# PCB-BI8-1x10SC3.net
KiCad netlist of a schematic drawn in EAGLE
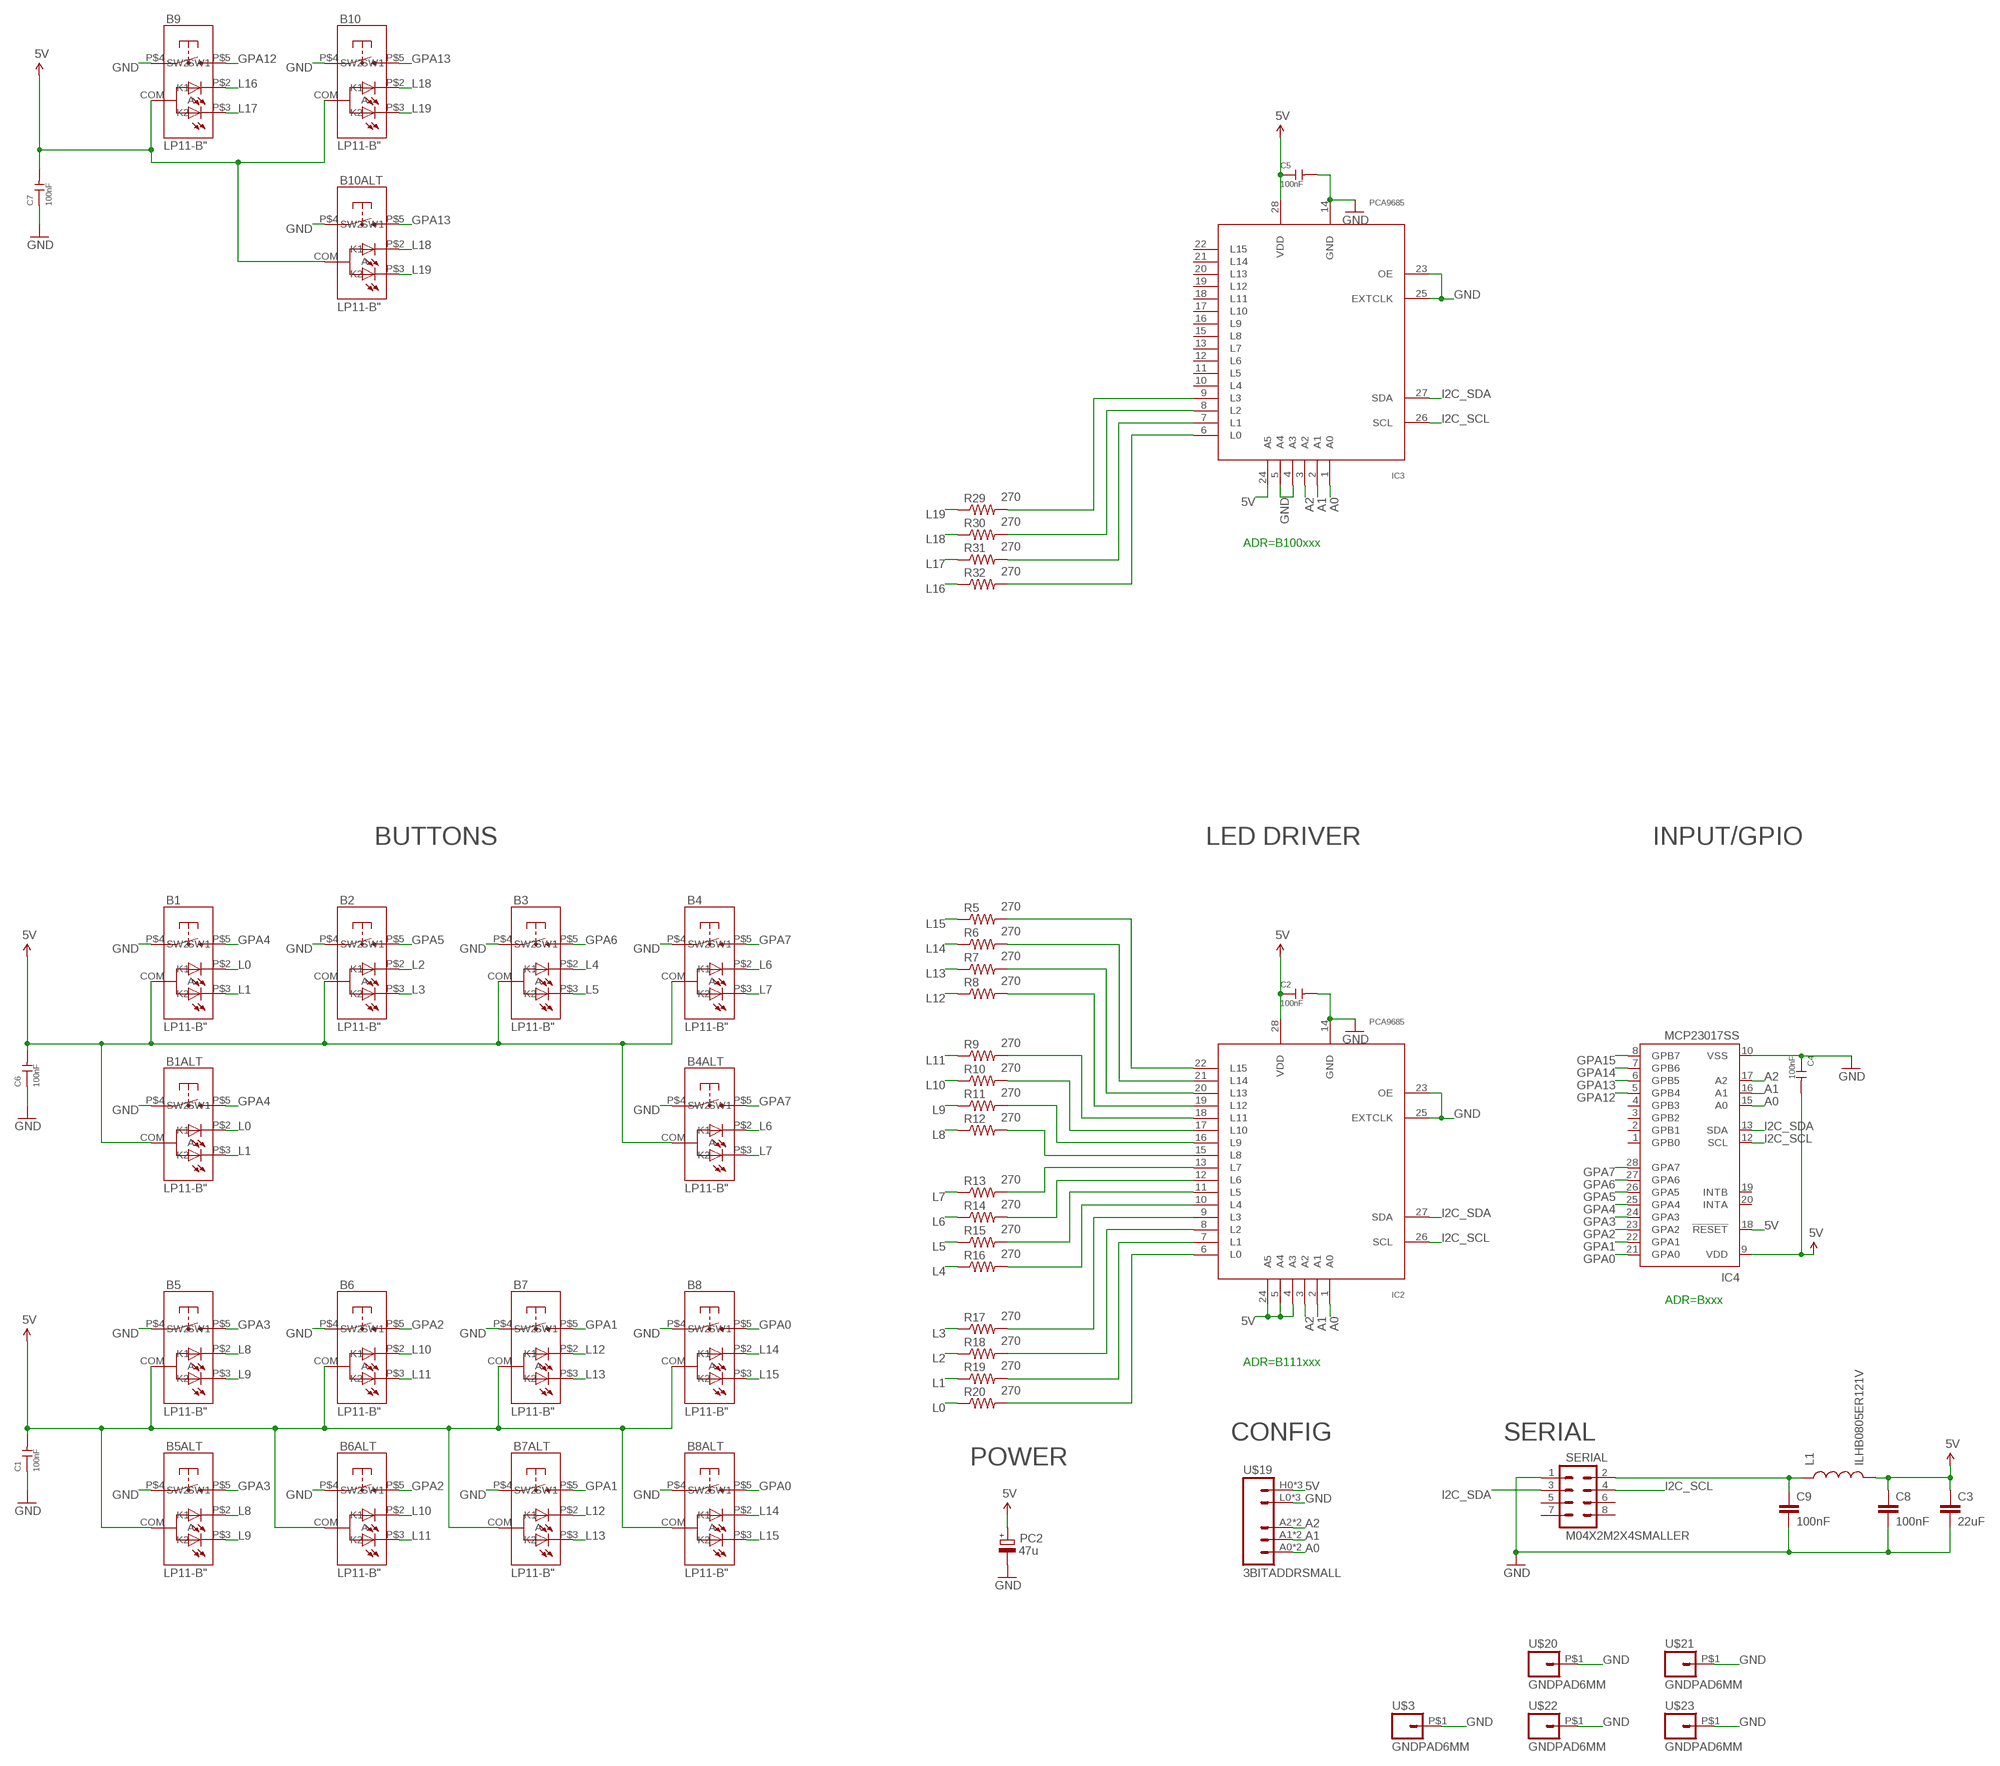
[diagram p0: schematic, sheet 1]

(export (version "E")
  (design (tool "Eeschema 10.0.6"))
  (components
    (comp (ref "B1")
      (value "LP11-B\"")
      (footprint "eagle-import:LP11")
      (libsource (lib "eagle-import") (part "LP11-B{dblquote}"))
    )
    (comp (ref "B1ALT")
      (value "LP11-B\"")
      (footprint "eagle-import:LP11")
      (libsource (lib "eagle-import") (part "LP11-B{dblquote}"))
    )
    (comp (ref "B2")
      (value "LP11-B\"")
      (footprint "eagle-import:LP11")
      (libsource (lib "eagle-import") (part "LP11-B{dblquote}"))
    )
    (comp (ref "B3")
      (value "LP11-B\"")
      (footprint "eagle-import:LP11")
      (libsource (lib "eagle-import") (part "LP11-B{dblquote}"))
    )
    (comp (ref "B4")
      (value "LP11-B\"")
      (footprint "eagle-import:LP11")
      (libsource (lib "eagle-import") (part "LP11-B{dblquote}"))
    )
    (comp (ref "B4ALT")
      (value "LP11-B\"")
      (footprint "eagle-import:LP11")
      (libsource (lib "eagle-import") (part "LP11-B{dblquote}"))
    )
    (comp (ref "B5")
      (value "LP11-B\"")
      (footprint "eagle-import:LP11")
      (libsource (lib "eagle-import") (part "LP11-B{dblquote}"))
    )
    (comp (ref "B5ALT")
      (value "LP11-B\"")
      (footprint "eagle-import:LP11")
      (libsource (lib "eagle-import") (part "LP11-B{dblquote}"))
    )
    (comp (ref "B6")
      (value "LP11-B\"")
      (footprint "eagle-import:LP11")
      (libsource (lib "eagle-import") (part "LP11-B{dblquote}"))
    )
    (comp (ref "B6ALT")
      (value "LP11-B\"")
      (footprint "eagle-import:LP11")
      (libsource (lib "eagle-import") (part "LP11-B{dblquote}"))
    )
    (comp (ref "B7")
      (value "LP11-B\"")
      (footprint "eagle-import:LP11")
      (libsource (lib "eagle-import") (part "LP11-B{dblquote}"))
    )
    (comp (ref "B7ALT")
      (value "LP11-B\"")
      (footprint "eagle-import:LP11")
      (libsource (lib "eagle-import") (part "LP11-B{dblquote}"))
    )
    (comp (ref "B8")
      (value "LP11-B\"")
      (footprint "eagle-import:LP11")
      (libsource (lib "eagle-import") (part "LP11-B{dblquote}"))
    )
    (comp (ref "B8ALT")
      (value "LP11-B\"")
      (footprint "eagle-import:LP11")
      (libsource (lib "eagle-import") (part "LP11-B{dblquote}"))
    )
    (comp (ref "B9")
      (value "LP11-B\"")
      (footprint "eagle-import:LP11")
      (libsource (lib "eagle-import") (part "LP11-B{dblquote}"))
    )
    (comp (ref "B10")
      (value "LP11-B\"")
      (footprint "eagle-import:LP11")
      (libsource (lib "eagle-import") (part "LP11-B{dblquote}"))
    )
    (comp (ref "B10ALT")
      (value "LP11-B\"")
      (footprint "eagle-import:LP11")
      (libsource (lib "eagle-import") (part "LP11-B{dblquote}"))
    )
    (comp (ref "C1")
      (value "100nF")
      (footprint "eagle-import:C0603")
      (libsource (lib "eagle-import") (part "CAP-0603"))
    )
    (comp (ref "C2")
      (value "100nF")
      (footprint "eagle-import:C0603")
      (libsource (lib "eagle-import") (part "CAP-0603"))
    )
    (comp (ref "C3")
      (value "22uF")
      (footprint "eagle-import:0805")
      (libsource (lib "eagle-import") (part "CAP0805"))
    )
    (comp (ref "C4")
      (value "100nF")
      (footprint "eagle-import:C0603")
      (libsource (lib "eagle-import") (part "CAP-0603"))
    )
    (comp (ref "C5")
      (value "100nF")
      (footprint "eagle-import:C0603")
      (libsource (lib "eagle-import") (part "CAP-0603"))
    )
    (comp (ref "C6")
      (value "100nF")
      (footprint "eagle-import:C0603")
      (libsource (lib "eagle-import") (part "CAP-0603"))
    )
    (comp (ref "C7")
      (value "100nF")
      (footprint "eagle-import:C0603")
      (libsource (lib "eagle-import") (part "CAP-0603"))
    )
    (comp (ref "C8")
      (value "100nF")
      (footprint "eagle-import:0603-CAP")
      (libsource (lib "eagle-import") (part "CAP0603-CAP"))
    )
    (comp (ref "C9")
      (value "100nF")
      (footprint "eagle-import:0603-CAP")
      (libsource (lib "eagle-import") (part "CAP0603-CAP"))
    )
    (comp (ref "IC2")
      (value "PCA9685")
      (footprint "eagle-import:TSSOP28")
      (libsource (lib "eagle-import") (part "PCA9685"))
    )
    (comp (ref "IC3")
      (value "PCA9685")
      (footprint "eagle-import:TSSOP28")
      (libsource (lib "eagle-import") (part "PCA9685"))
    )
    (comp (ref "IC4")
      (value "MCP23017SS")
      (footprint "eagle-import:SSOP28")
      (fields
        (field (name "MF") "MICROCHIP")
        (field (name "MPN") "MCP23017-E/SS")
        (field (name "MPN_1") "MCP23017-E/SS")
        (field (name "OC_FARNELL") "1467674")
        (field (name "OC_NEWARK") "31K2960")
      )
      (libsource (lib "eagle-import") (part "MCP23017SS"))
    )
    (comp (ref "L1")
      (value "ILHB0805ER121V")
      (footprint "eagle-import:0805")
      (libsource (lib "eagle-import") (part "INDUCTOR0805"))
    )
    (comp (ref "PC2")
      (value "47u")
      (footprint "eagle-import:PANASONIC_D")
      (libsource (lib "eagle-import") (part "CPOL-EUD"))
    )
    (comp (ref "R5")
      (value "270")
      (footprint "eagle-import:0603-RES")
      (libsource (lib "eagle-import") (part "RESISTOR0603-RES"))
    )
    (comp (ref "R6")
      (value "270")
      (footprint "eagle-import:0603-RES")
      (libsource (lib "eagle-import") (part "RESISTOR0603-RES"))
    )
    (comp (ref "R7")
      (value "270")
      (footprint "eagle-import:0603-RES")
      (libsource (lib "eagle-import") (part "RESISTOR0603-RES"))
    )
    (comp (ref "R8")
      (value "270")
      (footprint "eagle-import:0603-RES")
      (libsource (lib "eagle-import") (part "RESISTOR0603-RES"))
    )
    (comp (ref "R9")
      (value "270")
      (footprint "eagle-import:0603-RES")
      (libsource (lib "eagle-import") (part "RESISTOR0603-RES"))
    )
    (comp (ref "R10")
      (value "270")
      (footprint "eagle-import:0603-RES")
      (libsource (lib "eagle-import") (part "RESISTOR0603-RES"))
    )
    (comp (ref "R11")
      (value "270")
      (footprint "eagle-import:0603-RES")
      (libsource (lib "eagle-import") (part "RESISTOR0603-RES"))
    )
    (comp (ref "R12")
      (value "270")
      (footprint "eagle-import:0603-RES")
      (libsource (lib "eagle-import") (part "RESISTOR0603-RES"))
    )
    (comp (ref "R13")
      (value "270")
      (footprint "eagle-import:0603-RES")
      (libsource (lib "eagle-import") (part "RESISTOR0603-RES"))
    )
    (comp (ref "R14")
      (value "270")
      (footprint "eagle-import:0603-RES")
      (libsource (lib "eagle-import") (part "RESISTOR0603-RES"))
    )
    (comp (ref "R15")
      (value "270")
      (footprint "eagle-import:0603-RES")
      (libsource (lib "eagle-import") (part "RESISTOR0603-RES"))
    )
    (comp (ref "R16")
      (value "270")
      (footprint "eagle-import:0603-RES")
      (libsource (lib "eagle-import") (part "RESISTOR0603-RES"))
    )
    (comp (ref "R17")
      (value "270")
      (footprint "eagle-import:0603-RES")
      (libsource (lib "eagle-import") (part "RESISTOR0603-RES"))
    )
    (comp (ref "R18")
      (value "270")
      (footprint "eagle-import:0603-RES")
      (libsource (lib "eagle-import") (part "RESISTOR0603-RES"))
    )
    (comp (ref "R19")
      (value "270")
      (footprint "eagle-import:0603-RES")
      (libsource (lib "eagle-import") (part "RESISTOR0603-RES"))
    )
    (comp (ref "R20")
      (value "270")
      (footprint "eagle-import:0603-RES")
      (libsource (lib "eagle-import") (part "RESISTOR0603-RES"))
    )
    (comp (ref "R29")
      (value "270")
      (footprint "eagle-import:0603-RES")
      (libsource (lib "eagle-import") (part "RESISTOR0603-RES"))
    )
    (comp (ref "R30")
      (value "270")
      (footprint "eagle-import:0603-RES")
      (libsource (lib "eagle-import") (part "RESISTOR0603-RES"))
    )
    (comp (ref "R31")
      (value "270")
      (footprint "eagle-import:0603-RES")
      (libsource (lib "eagle-import") (part "RESISTOR0603-RES"))
    )
    (comp (ref "R32")
      (value "270")
      (footprint "eagle-import:0603-RES")
      (libsource (lib "eagle-import") (part "RESISTOR0603-RES"))
    )
    (comp (ref "SERIAL")
      (value "M04X2M2X4SMALLER")
      (footprint "eagle-import:M2X4SMALLER")
      (libsource (lib "eagle-import") (part "M04X2M2X4SMALLER"))
    )
    (comp (ref "U$3")
      (value "GNDPAD6MM")
      (footprint "eagle-import:3.2MMPAD6MM")
      (libsource (lib "eagle-import") (part "GNDPAD6MM"))
    )
    (comp (ref "U$19")
      (value "3BITADDRSMALL")
      (footprint "eagle-import:3BITADDR_SMALL")
      (libsource (lib "eagle-import") (part "3BITADDRSMALL"))
    )
    (comp (ref "U$20")
      (value "GNDPAD6MM")
      (footprint "eagle-import:3.2MMPAD6MM")
      (libsource (lib "eagle-import") (part "GNDPAD6MM"))
    )
    (comp (ref "U$21")
      (value "GNDPAD6MM")
      (footprint "eagle-import:3.2MMPAD6MM")
      (libsource (lib "eagle-import") (part "GNDPAD6MM"))
    )
    (comp (ref "U$22")
      (value "GNDPAD6MM")
      (footprint "eagle-import:3.2MMPAD6MM")
      (libsource (lib "eagle-import") (part "GNDPAD6MM"))
    )
    (comp (ref "U$23")
      (value "GNDPAD6MM")
      (footprint "eagle-import:3.2MMPAD6MM")
      (libsource (lib "eagle-import") (part "GNDPAD6MM"))
    )
  )
  (nets
    (net (code "1") (name "/A0") (class "Default")
      (node (ref "IC2") (pin "1") (pinfunction "A0_1") (pintype "input"))
      (node (ref "IC3") (pin "1") (pinfunction "A0_1") (pintype "input"))
      (node (ref "IC4") (pin "15") (pinfunction "A0_15") (pintype "input"))
      (node (ref "U$19") (pin "A0") (pinfunction "A0_A0") (pintype "passive"))
      (node (ref "U$19") (pin "AS0") (pinfunction "A0_AS0") (pintype "passive"))
    )
    (net (code "2") (name "/A1") (class "Default")
      (node (ref "IC2") (pin "2") (pinfunction "A1_2") (pintype "input"))
      (node (ref "IC3") (pin "2") (pinfunction "A1_2") (pintype "input"))
      (node (ref "IC4") (pin "16") (pinfunction "A1_16") (pintype "input"))
      (node (ref "U$19") (pin "A1") (pinfunction "A1_A1") (pintype "passive"))
      (node (ref "U$19") (pin "AS1") (pinfunction "A1_AS1") (pintype "passive"))
    )
    (net (code "3") (name "/A2") (class "Default")
      (node (ref "IC2") (pin "3") (pinfunction "A2_3") (pintype "input"))
      (node (ref "IC3") (pin "3") (pinfunction "A2_3") (pintype "input"))
      (node (ref "IC4") (pin "17") (pinfunction "A2_17") (pintype "input"))
      (node (ref "U$19") (pin "A2") (pinfunction "A2_A2") (pintype "passive"))
      (node (ref "U$19") (pin "AS2") (pinfunction "A2_AS2") (pintype "passive"))
    )
    (net (code "4") (name "/GPA0") (class "Default")
      (node (ref "B8") (pin "P$5") (pinfunction "SW2_P$5") (pintype "bidirectional"))
      (node (ref "B8ALT") (pin "P$5") (pinfunction "SW2_P$5") (pintype "bidirectional"))
      (node (ref "IC4") (pin "21") (pinfunction "GPA0_21") (pintype "bidirectional"))
    )
    (net (code "5") (name "/GPA1") (class "Default")
      (node (ref "B7") (pin "P$5") (pinfunction "SW2_P$5") (pintype "bidirectional"))
      (node (ref "B7ALT") (pin "P$5") (pinfunction "SW2_P$5") (pintype "bidirectional"))
      (node (ref "IC4") (pin "22") (pinfunction "GPA1_22") (pintype "bidirectional"))
    )
    (net (code "6") (name "/GPA2") (class "Default")
      (node (ref "B6") (pin "P$5") (pinfunction "SW2_P$5") (pintype "bidirectional"))
      (node (ref "B6ALT") (pin "P$5") (pinfunction "SW2_P$5") (pintype "bidirectional"))
      (node (ref "IC4") (pin "23") (pinfunction "GPA2_23") (pintype "bidirectional"))
    )
    (net (code "7") (name "/GPA3") (class "Default")
      (node (ref "B5") (pin "P$5") (pinfunction "SW2_P$5") (pintype "bidirectional"))
      (node (ref "B5ALT") (pin "P$5") (pinfunction "SW2_P$5") (pintype "bidirectional"))
      (node (ref "IC4") (pin "24") (pinfunction "GPA3_24") (pintype "bidirectional"))
    )
    (net (code "8") (name "/GPA4") (class "Default")
      (node (ref "B1") (pin "P$5") (pinfunction "SW2_P$5") (pintype "bidirectional"))
      (node (ref "B1ALT") (pin "P$5") (pinfunction "SW2_P$5") (pintype "bidirectional"))
      (node (ref "IC4") (pin "25") (pinfunction "GPA4_25") (pintype "bidirectional"))
    )
    (net (code "9") (name "/GPA5") (class "Default")
      (node (ref "B2") (pin "P$5") (pinfunction "SW2_P$5") (pintype "bidirectional"))
      (node (ref "IC4") (pin "26") (pinfunction "GPA5_26") (pintype "bidirectional"))
    )
    (net (code "10") (name "/GPA6") (class "Default")
      (node (ref "B3") (pin "P$5") (pinfunction "SW2_P$5") (pintype "bidirectional"))
      (node (ref "IC4") (pin "27") (pinfunction "GPA6_27") (pintype "bidirectional"))
    )
    (net (code "11") (name "/GPA7") (class "Default")
      (node (ref "B4") (pin "P$5") (pinfunction "SW2_P$5") (pintype "bidirectional"))
      (node (ref "B4ALT") (pin "P$5") (pinfunction "SW2_P$5") (pintype "bidirectional"))
      (node (ref "IC4") (pin "28") (pinfunction "GPA7_28") (pintype "bidirectional"))
    )
    (net (code "12") (name "/GPA12") (class "Default")
      (node (ref "B9") (pin "P$5") (pinfunction "SW2_P$5") (pintype "bidirectional"))
      (node (ref "IC4") (pin "5") (pinfunction "GPB4_5") (pintype "bidirectional"))
    )
    (net (code "13") (name "/GPA13") (class "Default")
      (node (ref "B10") (pin "P$5") (pinfunction "SW2_P$5") (pintype "bidirectional"))
      (node (ref "B10ALT") (pin "P$5") (pinfunction "SW2_P$5") (pintype "bidirectional"))
      (node (ref "IC4") (pin "6") (pinfunction "GPB5_6") (pintype "bidirectional"))
    )
    (net (code "14") (name "/GPA14") (class "Default")
      (node (ref "IC4") (pin "7") (pinfunction "GPB6_7") (pintype "bidirectional"))
    )
    (net (code "15") (name "/GPA15") (class "Default")
      (node (ref "IC4") (pin "8") (pinfunction "GPB7_8") (pintype "bidirectional"))
    )
    (net (code "16") (name "/I2C_SCL") (class "Default")
      (node (ref "IC2") (pin "26") (pinfunction "SCL_26") (pintype "input"))
      (node (ref "IC3") (pin "26") (pinfunction "SCL_26") (pintype "input"))
      (node (ref "IC4") (pin "12") (pinfunction "SCL_12") (pintype "input"))
      (node (ref "SERIAL") (pin "4") (pinfunction "4_4") (pintype "passive"))
    )
    (net (code "17") (name "/I2C_SDA") (class "Default")
      (node (ref "IC2") (pin "27") (pinfunction "SDA_27") (pintype "input"))
      (node (ref "IC3") (pin "27") (pinfunction "SDA_27") (pintype "input"))
      (node (ref "IC4") (pin "13") (pinfunction "SDA_13") (pintype "bidirectional"))
      (node (ref "SERIAL") (pin "3") (pinfunction "3_3") (pintype "passive"))
    )
    (net (code "18") (name "/L0") (class "Default")
      (node (ref "B1") (pin "P$2") (pinfunction "K1_P$2") (pintype "bidirectional"))
      (node (ref "B1ALT") (pin "P$2") (pinfunction "K1_P$2") (pintype "bidirectional"))
      (node (ref "R20") (pin "1") (pinfunction "1_1") (pintype "passive"))
    )
    (net (code "19") (name "/L1") (class "Default")
      (node (ref "B1") (pin "P$3") (pinfunction "K2_P$3") (pintype "bidirectional"))
      (node (ref "B1ALT") (pin "P$3") (pinfunction "K2_P$3") (pintype "bidirectional"))
      (node (ref "R19") (pin "1") (pinfunction "1_1") (pintype "passive"))
    )
    (net (code "20") (name "/L2") (class "Default")
      (node (ref "B2") (pin "P$2") (pinfunction "K1_P$2") (pintype "bidirectional"))
      (node (ref "R18") (pin "1") (pinfunction "1_1") (pintype "passive"))
    )
    (net (code "21") (name "/L3") (class "Default")
      (node (ref "B2") (pin "P$3") (pinfunction "K2_P$3") (pintype "bidirectional"))
      (node (ref "R17") (pin "1") (pinfunction "1_1") (pintype "passive"))
    )
    (net (code "22") (name "/L4") (class "Default")
      (node (ref "B3") (pin "P$2") (pinfunction "K1_P$2") (pintype "bidirectional"))
      (node (ref "R16") (pin "1") (pinfunction "1_1") (pintype "passive"))
    )
    (net (code "23") (name "/L5") (class "Default")
      (node (ref "B3") (pin "P$3") (pinfunction "K2_P$3") (pintype "bidirectional"))
      (node (ref "R15") (pin "1") (pinfunction "1_1") (pintype "passive"))
    )
    (net (code "24") (name "/L6") (class "Default")
      (node (ref "B4") (pin "P$2") (pinfunction "K1_P$2") (pintype "bidirectional"))
      (node (ref "B4ALT") (pin "P$2") (pinfunction "K1_P$2") (pintype "bidirectional"))
      (node (ref "R14") (pin "1") (pinfunction "1_1") (pintype "passive"))
    )
    (net (code "25") (name "/L7") (class "Default")
      (node (ref "B4") (pin "P$3") (pinfunction "K2_P$3") (pintype "bidirectional"))
      (node (ref "B4ALT") (pin "P$3") (pinfunction "K2_P$3") (pintype "bidirectional"))
      (node (ref "R13") (pin "1") (pinfunction "1_1") (pintype "passive"))
    )
    (net (code "26") (name "/L8") (class "Default")
      (node (ref "B5") (pin "P$2") (pinfunction "K1_P$2") (pintype "bidirectional"))
      (node (ref "B5ALT") (pin "P$2") (pinfunction "K1_P$2") (pintype "bidirectional"))
      (node (ref "R12") (pin "1") (pinfunction "1_1") (pintype "passive"))
    )
    (net (code "27") (name "/L9") (class "Default")
      (node (ref "B5") (pin "P$3") (pinfunction "K2_P$3") (pintype "bidirectional"))
      (node (ref "B5ALT") (pin "P$3") (pinfunction "K2_P$3") (pintype "bidirectional"))
      (node (ref "R11") (pin "1") (pinfunction "1_1") (pintype "passive"))
    )
    (net (code "28") (name "/L10") (class "Default")
      (node (ref "B6") (pin "P$2") (pinfunction "K1_P$2") (pintype "bidirectional"))
      (node (ref "B6ALT") (pin "P$2") (pinfunction "K1_P$2") (pintype "bidirectional"))
      (node (ref "R10") (pin "1") (pinfunction "1_1") (pintype "passive"))
    )
    (net (code "29") (name "/L11") (class "Default")
      (node (ref "B6") (pin "P$3") (pinfunction "K2_P$3") (pintype "bidirectional"))
      (node (ref "B6ALT") (pin "P$3") (pinfunction "K2_P$3") (pintype "bidirectional"))
      (node (ref "R9") (pin "1") (pinfunction "1_1") (pintype "passive"))
    )
    (net (code "30") (name "/L12") (class "Default")
      (node (ref "B7") (pin "P$2") (pinfunction "K1_P$2") (pintype "bidirectional"))
      (node (ref "B7ALT") (pin "P$2") (pinfunction "K1_P$2") (pintype "bidirectional"))
      (node (ref "R8") (pin "1") (pinfunction "1_1") (pintype "passive"))
    )
    (net (code "31") (name "/L13") (class "Default")
      (node (ref "B7") (pin "P$3") (pinfunction "K2_P$3") (pintype "bidirectional"))
      (node (ref "B7ALT") (pin "P$3") (pinfunction "K2_P$3") (pintype "bidirectional"))
      (node (ref "R7") (pin "1") (pinfunction "1_1") (pintype "passive"))
    )
    (net (code "32") (name "/L14") (class "Default")
      (node (ref "B8") (pin "P$2") (pinfunction "K1_P$2") (pintype "bidirectional"))
      (node (ref "B8ALT") (pin "P$2") (pinfunction "K1_P$2") (pintype "bidirectional"))
      (node (ref "R6") (pin "1") (pinfunction "1_1") (pintype "passive"))
    )
    (net (code "33") (name "/L15") (class "Default")
      (node (ref "B8") (pin "P$3") (pinfunction "K2_P$3") (pintype "bidirectional"))
      (node (ref "B8ALT") (pin "P$3") (pinfunction "K2_P$3") (pintype "bidirectional"))
      (node (ref "R5") (pin "1") (pinfunction "1_1") (pintype "passive"))
    )
    (net (code "34") (name "/L16") (class "Default")
      (node (ref "B9") (pin "P$2") (pinfunction "K1_P$2") (pintype "bidirectional"))
      (node (ref "R32") (pin "1") (pinfunction "1_1") (pintype "passive"))
    )
    (net (code "35") (name "/L17") (class "Default")
      (node (ref "B9") (pin "P$3") (pinfunction "K2_P$3") (pintype "bidirectional"))
      (node (ref "R31") (pin "1") (pinfunction "1_1") (pintype "passive"))
    )
    (net (code "36") (name "/L18") (class "Default")
      (node (ref "B10") (pin "P$2") (pinfunction "K1_P$2") (pintype "bidirectional"))
      (node (ref "B10ALT") (pin "P$2") (pinfunction "K1_P$2") (pintype "bidirectional"))
      (node (ref "R30") (pin "1") (pinfunction "1_1") (pintype "passive"))
    )
    (net (code "37") (name "/L19") (class "Default")
      (node (ref "B10") (pin "P$3") (pinfunction "K2_P$3") (pintype "bidirectional"))
      (node (ref "B10ALT") (pin "P$3") (pinfunction "K2_P$3") (pintype "bidirectional"))
      (node (ref "R29") (pin "1") (pinfunction "1_1") (pintype "passive"))
    )
    (net (code "38") (name "5V") (class "Default")
      (node (ref "B1") (pin "COM") (pinfunction "A_COM") (pintype "bidirectional"))
      (node (ref "B10") (pin "COM") (pinfunction "A_COM") (pintype "bidirectional"))
      (node (ref "B10ALT") (pin "COM") (pinfunction "A_COM") (pintype "bidirectional"))
      (node (ref "B1ALT") (pin "COM") (pinfunction "A_COM") (pintype "bidirectional"))
      (node (ref "B2") (pin "COM") (pinfunction "A_COM") (pintype "bidirectional"))
      (node (ref "B3") (pin "COM") (pinfunction "A_COM") (pintype "bidirectional"))
      (node (ref "B4") (pin "COM") (pinfunction "A_COM") (pintype "bidirectional"))
      (node (ref "B4ALT") (pin "COM") (pinfunction "A_COM") (pintype "bidirectional"))
      (node (ref "B5") (pin "COM") (pinfunction "A_COM") (pintype "bidirectional"))
      (node (ref "B5ALT") (pin "COM") (pinfunction "A_COM") (pintype "bidirectional"))
      (node (ref "B6") (pin "COM") (pinfunction "A_COM") (pintype "bidirectional"))
      (node (ref "B6ALT") (pin "COM") (pinfunction "A_COM") (pintype "bidirectional"))
      (node (ref "B7") (pin "COM") (pinfunction "A_COM") (pintype "bidirectional"))
      (node (ref "B7ALT") (pin "COM") (pinfunction "A_COM") (pintype "bidirectional"))
      (node (ref "B8") (pin "COM") (pinfunction "A_COM") (pintype "bidirectional"))
      (node (ref "B8ALT") (pin "COM") (pinfunction "A_COM") (pintype "bidirectional"))
      (node (ref "B9") (pin "COM") (pinfunction "A_COM") (pintype "bidirectional"))
      (node (ref "C1") (pin "2") (pinfunction "2_2") (pintype "passive"))
      (node (ref "C2") (pin "1") (pinfunction "1_1") (pintype "passive"))
      (node (ref "C3") (pin "1") (pinfunction "1_1") (pintype "passive"))
      (node (ref "C4") (pin "2") (pinfunction "2_2") (pintype "passive"))
      (node (ref "C5") (pin "1") (pinfunction "1_1") (pintype "passive"))
      (node (ref "C6") (pin "2") (pinfunction "2_2") (pintype "passive"))
      (node (ref "C7") (pin "2") (pinfunction "2_2") (pintype "passive"))
      (node (ref "C8") (pin "1") (pinfunction "1_1") (pintype "passive"))
      (node (ref "IC2") (pin "24") (pinfunction "A5_24") (pintype "input"))
      (node (ref "IC2") (pin "28") (pinfunction "VDD_28") (pintype "power_in"))
      (node (ref "IC2") (pin "4") (pinfunction "A3_4") (pintype "input"))
      (node (ref "IC2") (pin "5") (pinfunction "A4_5") (pintype "input"))
      (node (ref "IC3") (pin "24") (pinfunction "A5_24") (pintype "input"))
      (node (ref "IC3") (pin "28") (pinfunction "VDD_28") (pintype "power_in"))
      (node (ref "IC4") (pin "18") (pinfunction "~{RESET}_18") (pintype "input"))
      (node (ref "IC4") (pin "9") (pinfunction "VDD_9") (pintype "power_in"))
      (node (ref "L1") (pin "2") (pinfunction "2_2") (pintype "passive"))
      (node (ref "PC2") (pin "+") (pinfunction "+_+") (pintype "passive"))
      (node (ref "U$19") (pin "H0") (pinfunction "VCC_H0") (pintype "passive"))
      (node (ref "U$19") (pin "H1") (pinfunction "VCC_H1") (pintype "passive"))
      (node (ref "U$19") (pin "H2") (pinfunction "VCC_H2") (pintype "passive"))
    )
    (net (code "39") (name "GND") (class "Default")
      (node (ref "B1") (pin "P$4") (pinfunction "SW1_P$4") (pintype "bidirectional"))
      (node (ref "B10") (pin "P$4") (pinfunction "SW1_P$4") (pintype "bidirectional"))
      (node (ref "B10ALT") (pin "P$4") (pinfunction "SW1_P$4") (pintype "bidirectional"))
      (node (ref "B1ALT") (pin "P$4") (pinfunction "SW1_P$4") (pintype "bidirectional"))
      (node (ref "B2") (pin "P$4") (pinfunction "SW1_P$4") (pintype "bidirectional"))
      (node (ref "B3") (pin "P$4") (pinfunction "SW1_P$4") (pintype "bidirectional"))
      (node (ref "B4") (pin "P$4") (pinfunction "SW1_P$4") (pintype "bidirectional"))
      (node (ref "B4ALT") (pin "P$4") (pinfunction "SW1_P$4") (pintype "bidirectional"))
      (node (ref "B5") (pin "P$4") (pinfunction "SW1_P$4") (pintype "bidirectional"))
      (node (ref "B5ALT") (pin "P$4") (pinfunction "SW1_P$4") (pintype "bidirectional"))
      (node (ref "B6") (pin "P$4") (pinfunction "SW1_P$4") (pintype "bidirectional"))
      (node (ref "B6ALT") (pin "P$4") (pinfunction "SW1_P$4") (pintype "bidirectional"))
      (node (ref "B7") (pin "P$4") (pinfunction "SW1_P$4") (pintype "bidirectional"))
      (node (ref "B7ALT") (pin "P$4") (pinfunction "SW1_P$4") (pintype "bidirectional"))
      (node (ref "B8") (pin "P$4") (pinfunction "SW1_P$4") (pintype "bidirectional"))
      (node (ref "B8ALT") (pin "P$4") (pinfunction "SW1_P$4") (pintype "bidirectional"))
      (node (ref "B9") (pin "P$4") (pinfunction "SW1_P$4") (pintype "bidirectional"))
      (node (ref "C1") (pin "1") (pinfunction "1_1") (pintype "passive"))
      (node (ref "C2") (pin "2") (pinfunction "2_2") (pintype "passive"))
      (node (ref "C3") (pin "2") (pinfunction "2_2") (pintype "passive"))
      (node (ref "C4") (pin "1") (pinfunction "1_1") (pintype "passive"))
      (node (ref "C5") (pin "2") (pinfunction "2_2") (pintype "passive"))
      (node (ref "C6") (pin "1") (pinfunction "1_1") (pintype "passive"))
      (node (ref "C7") (pin "1") (pinfunction "1_1") (pintype "passive"))
      (node (ref "C8") (pin "2") (pinfunction "2_2") (pintype "passive"))
      (node (ref "C9") (pin "2") (pinfunction "2_2") (pintype "passive"))
      (node (ref "IC2") (pin "14") (pinfunction "GND_14") (pintype "power_in"))
      (node (ref "IC2") (pin "23") (pinfunction "OE_23") (pintype "input"))
      (node (ref "IC2") (pin "25") (pinfunction "EXTCLK_25") (pintype "input"))
      (node (ref "IC3") (pin "14") (pinfunction "GND_14") (pintype "power_in"))
      (node (ref "IC3") (pin "23") (pinfunction "OE_23") (pintype "input"))
      (node (ref "IC3") (pin "25") (pinfunction "EXTCLK_25") (pintype "input"))
      (node (ref "IC3") (pin "4") (pinfunction "A3_4") (pintype "input"))
      (node (ref "IC3") (pin "5") (pinfunction "A4_5") (pintype "input"))
      (node (ref "IC4") (pin "10") (pinfunction "VSS_10") (pintype "power_in"))
      (node (ref "PC2") (pin "-") (pinfunction "-_-") (pintype "passive"))
      (node (ref "SERIAL") (pin "1") (pinfunction "1_1") (pintype "passive"))
      (node (ref "U$19") (pin "L0") (pinfunction "GND_L0") (pintype "passive"))
      (node (ref "U$19") (pin "L1") (pinfunction "GND_L1") (pintype "passive"))
      (node (ref "U$19") (pin "L2") (pinfunction "GND_L2") (pintype "passive"))
      (node (ref "U$20") (pin "P$1") (pinfunction "1_P$1") (pintype "passive"))
      (node (ref "U$21") (pin "P$1") (pinfunction "1_P$1") (pintype "passive"))
      (node (ref "U$22") (pin "P$1") (pinfunction "1_P$1") (pintype "passive"))
      (node (ref "U$23") (pin "P$1") (pinfunction "1_P$1") (pintype "passive"))
      (node (ref "U$3") (pin "P$1") (pinfunction "1_P$1") (pintype "passive"))
    )
    (net (code "40") (name "Net-(C9-Pad1)") (class "Default")
      (node (ref "C9") (pin "1") (pinfunction "1_1") (pintype "passive"))
      (node (ref "L1") (pin "1") (pinfunction "1_1") (pintype "passive"))
      (node (ref "SERIAL") (pin "2") (pinfunction "2_2") (pintype "passive"))
    )
    (net (code "41") (name "Net-(IC2-L0)") (class "Default")
      (node (ref "IC2") (pin "6") (pinfunction "L0_6") (pintype "output"))
      (node (ref "R20") (pin "2") (pinfunction "2_2") (pintype "passive"))
    )
    (net (code "42") (name "Net-(IC2-L1)") (class "Default")
      (node (ref "IC2") (pin "7") (pinfunction "L1_7") (pintype "output"))
      (node (ref "R19") (pin "2") (pinfunction "2_2") (pintype "passive"))
    )
    (net (code "43") (name "Net-(IC2-L2)") (class "Default")
      (node (ref "IC2") (pin "8") (pinfunction "L2_8") (pintype "output"))
      (node (ref "R18") (pin "2") (pinfunction "2_2") (pintype "passive"))
    )
    (net (code "44") (name "Net-(IC2-L3)") (class "Default")
      (node (ref "IC2") (pin "9") (pinfunction "L3_9") (pintype "output"))
      (node (ref "R17") (pin "2") (pinfunction "2_2") (pintype "passive"))
    )
    (net (code "45") (name "Net-(IC2-L4)") (class "Default")
      (node (ref "IC2") (pin "10") (pinfunction "L4_10") (pintype "output"))
      (node (ref "R16") (pin "2") (pinfunction "2_2") (pintype "passive"))
    )
    (net (code "46") (name "Net-(IC2-L5)") (class "Default")
      (node (ref "IC2") (pin "11") (pinfunction "L5_11") (pintype "output"))
      (node (ref "R15") (pin "2") (pinfunction "2_2") (pintype "passive"))
    )
    (net (code "47") (name "Net-(IC2-L6)") (class "Default")
      (node (ref "IC2") (pin "12") (pinfunction "L6_12") (pintype "output"))
      (node (ref "R14") (pin "2") (pinfunction "2_2") (pintype "passive"))
    )
    (net (code "48") (name "Net-(IC2-L7)") (class "Default")
      (node (ref "IC2") (pin "13") (pinfunction "L7_13") (pintype "output"))
      (node (ref "R13") (pin "2") (pinfunction "2_2") (pintype "passive"))
    )
    (net (code "49") (name "Net-(IC2-L8)") (class "Default")
      (node (ref "IC2") (pin "15") (pinfunction "L8_15") (pintype "output"))
      (node (ref "R12") (pin "2") (pinfunction "2_2") (pintype "passive"))
    )
    (net (code "50") (name "Net-(IC2-L9)") (class "Default")
      (node (ref "IC2") (pin "16") (pinfunction "L9_16") (pintype "output"))
      (node (ref "R11") (pin "2") (pinfunction "2_2") (pintype "passive"))
    )
    (net (code "51") (name "Net-(IC2-L10)") (class "Default")
      (node (ref "IC2") (pin "17") (pinfunction "L10_17") (pintype "output"))
      (node (ref "R10") (pin "2") (pinfunction "2_2") (pintype "passive"))
    )
    (net (code "52") (name "Net-(IC2-L11)") (class "Default")
      (node (ref "IC2") (pin "18") (pinfunction "L11_18") (pintype "output"))
      (node (ref "R9") (pin "2") (pinfunction "2_2") (pintype "passive"))
    )
    (net (code "53") (name "Net-(IC2-L12)") (class "Default")
      (node (ref "IC2") (pin "19") (pinfunction "L12_19") (pintype "output"))
      (node (ref "R8") (pin "2") (pinfunction "2_2") (pintype "passive"))
    )
    (net (code "54") (name "Net-(IC2-L13)") (class "Default")
      (node (ref "IC2") (pin "20") (pinfunction "L13_20") (pintype "output"))
      (node (ref "R7") (pin "2") (pinfunction "2_2") (pintype "passive"))
    )
    (net (code "55") (name "Net-(IC2-L14)") (class "Default")
      (node (ref "IC2") (pin "21") (pinfunction "L14_21") (pintype "output"))
      (node (ref "R6") (pin "2") (pinfunction "2_2") (pintype "passive"))
    )
    (net (code "56") (name "Net-(IC2-L15)") (class "Default")
      (node (ref "IC2") (pin "22") (pinfunction "L15_22") (pintype "output"))
      (node (ref "R5") (pin "2") (pinfunction "2_2") (pintype "passive"))
    )
    (net (code "57") (name "Net-(IC3-L0)") (class "Default")
      (node (ref "IC3") (pin "6") (pinfunction "L0_6") (pintype "output"))
      (node (ref "R32") (pin "2") (pinfunction "2_2") (pintype "passive"))
    )
    (net (code "58") (name "Net-(IC3-L1)") (class "Default")
      (node (ref "IC3") (pin "7") (pinfunction "L1_7") (pintype "output"))
      (node (ref "R31") (pin "2") (pinfunction "2_2") (pintype "passive"))
    )
    (net (code "59") (name "Net-(IC3-L2)") (class "Default")
      (node (ref "IC3") (pin "8") (pinfunction "L2_8") (pintype "output"))
      (node (ref "R30") (pin "2") (pinfunction "2_2") (pintype "passive"))
    )
    (net (code "60") (name "Net-(IC3-L3)") (class "Default")
      (node (ref "IC3") (pin "9") (pinfunction "L3_9") (pintype "output"))
      (node (ref "R29") (pin "2") (pinfunction "2_2") (pintype "passive"))
    )
    (net (code "61") (name "unconnected-(IC3-L4-Pad10)") (class "Default")
      (node (ref "IC3") (pin "10") (pinfunction "L4_10") (pintype "output"))
    )
    (net (code "62") (name "unconnected-(IC3-L5-Pad11)") (class "Default")
      (node (ref "IC3") (pin "11") (pinfunction "L5_11") (pintype "output"))
    )
    (net (code "63") (name "unconnected-(IC3-L6-Pad12)") (class "Default")
      (node (ref "IC3") (pin "12") (pinfunction "L6_12") (pintype "output"))
    )
    (net (code "64") (name "unconnected-(IC3-L7-Pad13)") (class "Default")
      (node (ref "IC3") (pin "13") (pinfunction "L7_13") (pintype "output"))
    )
    (net (code "65") (name "unconnected-(IC3-L8-Pad15)") (class "Default")
      (node (ref "IC3") (pin "15") (pinfunction "L8_15") (pintype "output"))
    )
    (net (code "66") (name "unconnected-(IC3-L9-Pad16)") (class "Default")
      (node (ref "IC3") (pin "16") (pinfunction "L9_16") (pintype "output"))
    )
    (net (code "67") (name "unconnected-(IC3-L10-Pad17)") (class "Default")
      (node (ref "IC3") (pin "17") (pinfunction "L10_17") (pintype "output"))
    )
    (net (code "68") (name "unconnected-(IC3-L11-Pad18)") (class "Default")
      (node (ref "IC3") (pin "18") (pinfunction "L11_18") (pintype "output"))
    )
    (net (code "69") (name "unconnected-(IC3-L12-Pad19)") (class "Default")
      (node (ref "IC3") (pin "19") (pinfunction "L12_19") (pintype "output"))
    )
    (net (code "70") (name "unconnected-(IC3-L13-Pad20)") (class "Default")
      (node (ref "IC3") (pin "20") (pinfunction "L13_20") (pintype "output"))
    )
    (net (code "71") (name "unconnected-(IC3-L14-Pad21)") (class "Default")
      (node (ref "IC3") (pin "21") (pinfunction "L14_21") (pintype "output"))
    )
    (net (code "72") (name "unconnected-(IC3-L15-Pad22)") (class "Default")
      (node (ref "IC3") (pin "22") (pinfunction "L15_22") (pintype "output"))
    )
    (net (code "73") (name "unconnected-(IC4-GPB0-Pad1)") (class "Default")
      (node (ref "IC4") (pin "1") (pinfunction "GPB0_1") (pintype "bidirectional"))
    )
    (net (code "74") (name "unconnected-(IC4-GPB1-Pad2)") (class "Default")
      (node (ref "IC4") (pin "2") (pinfunction "GPB1_2") (pintype "bidirectional"))
    )
    (net (code "75") (name "unconnected-(IC4-GPB2-Pad3)") (class "Default")
      (node (ref "IC4") (pin "3") (pinfunction "GPB2_3") (pintype "bidirectional"))
    )
    (net (code "76") (name "unconnected-(IC4-GPB3-Pad4)") (class "Default")
      (node (ref "IC4") (pin "4") (pinfunction "GPB3_4") (pintype "bidirectional"))
    )
    (net (code "77") (name "unconnected-(IC4-INTA-Pad20)") (class "Default")
      (node (ref "IC4") (pin "20") (pinfunction "INTA_20") (pintype "output"))
    )
    (net (code "78") (name "unconnected-(IC4-INTB-Pad19)") (class "Default")
      (node (ref "IC4") (pin "19") (pinfunction "INTB_19") (pintype "output"))
    )
    (net (code "79") (name "unconnected-(SERIAL-Pad5)") (class "Default")
      (node (ref "SERIAL") (pin "5") (pinfunction "5_5") (pintype "passive"))
    )
    (net (code "80") (name "unconnected-(SERIAL-Pad6)") (class "Default")
      (node (ref "SERIAL") (pin "6") (pinfunction "6_6") (pintype "passive"))
    )
    (net (code "81") (name "unconnected-(SERIAL-Pad7)") (class "Default")
      (node (ref "SERIAL") (pin "7") (pinfunction "7_7") (pintype "passive"))
    )
    (net (code "82") (name "unconnected-(SERIAL-Pad8)") (class "Default")
      (node (ref "SERIAL") (pin "8") (pinfunction "8_8") (pintype "passive"))
    )
  )
)
